# SCH_Remote_Recovery_Switch_Mini_v1_2025-.net
KiCad netlist of a schematic drawn in EasyEDA
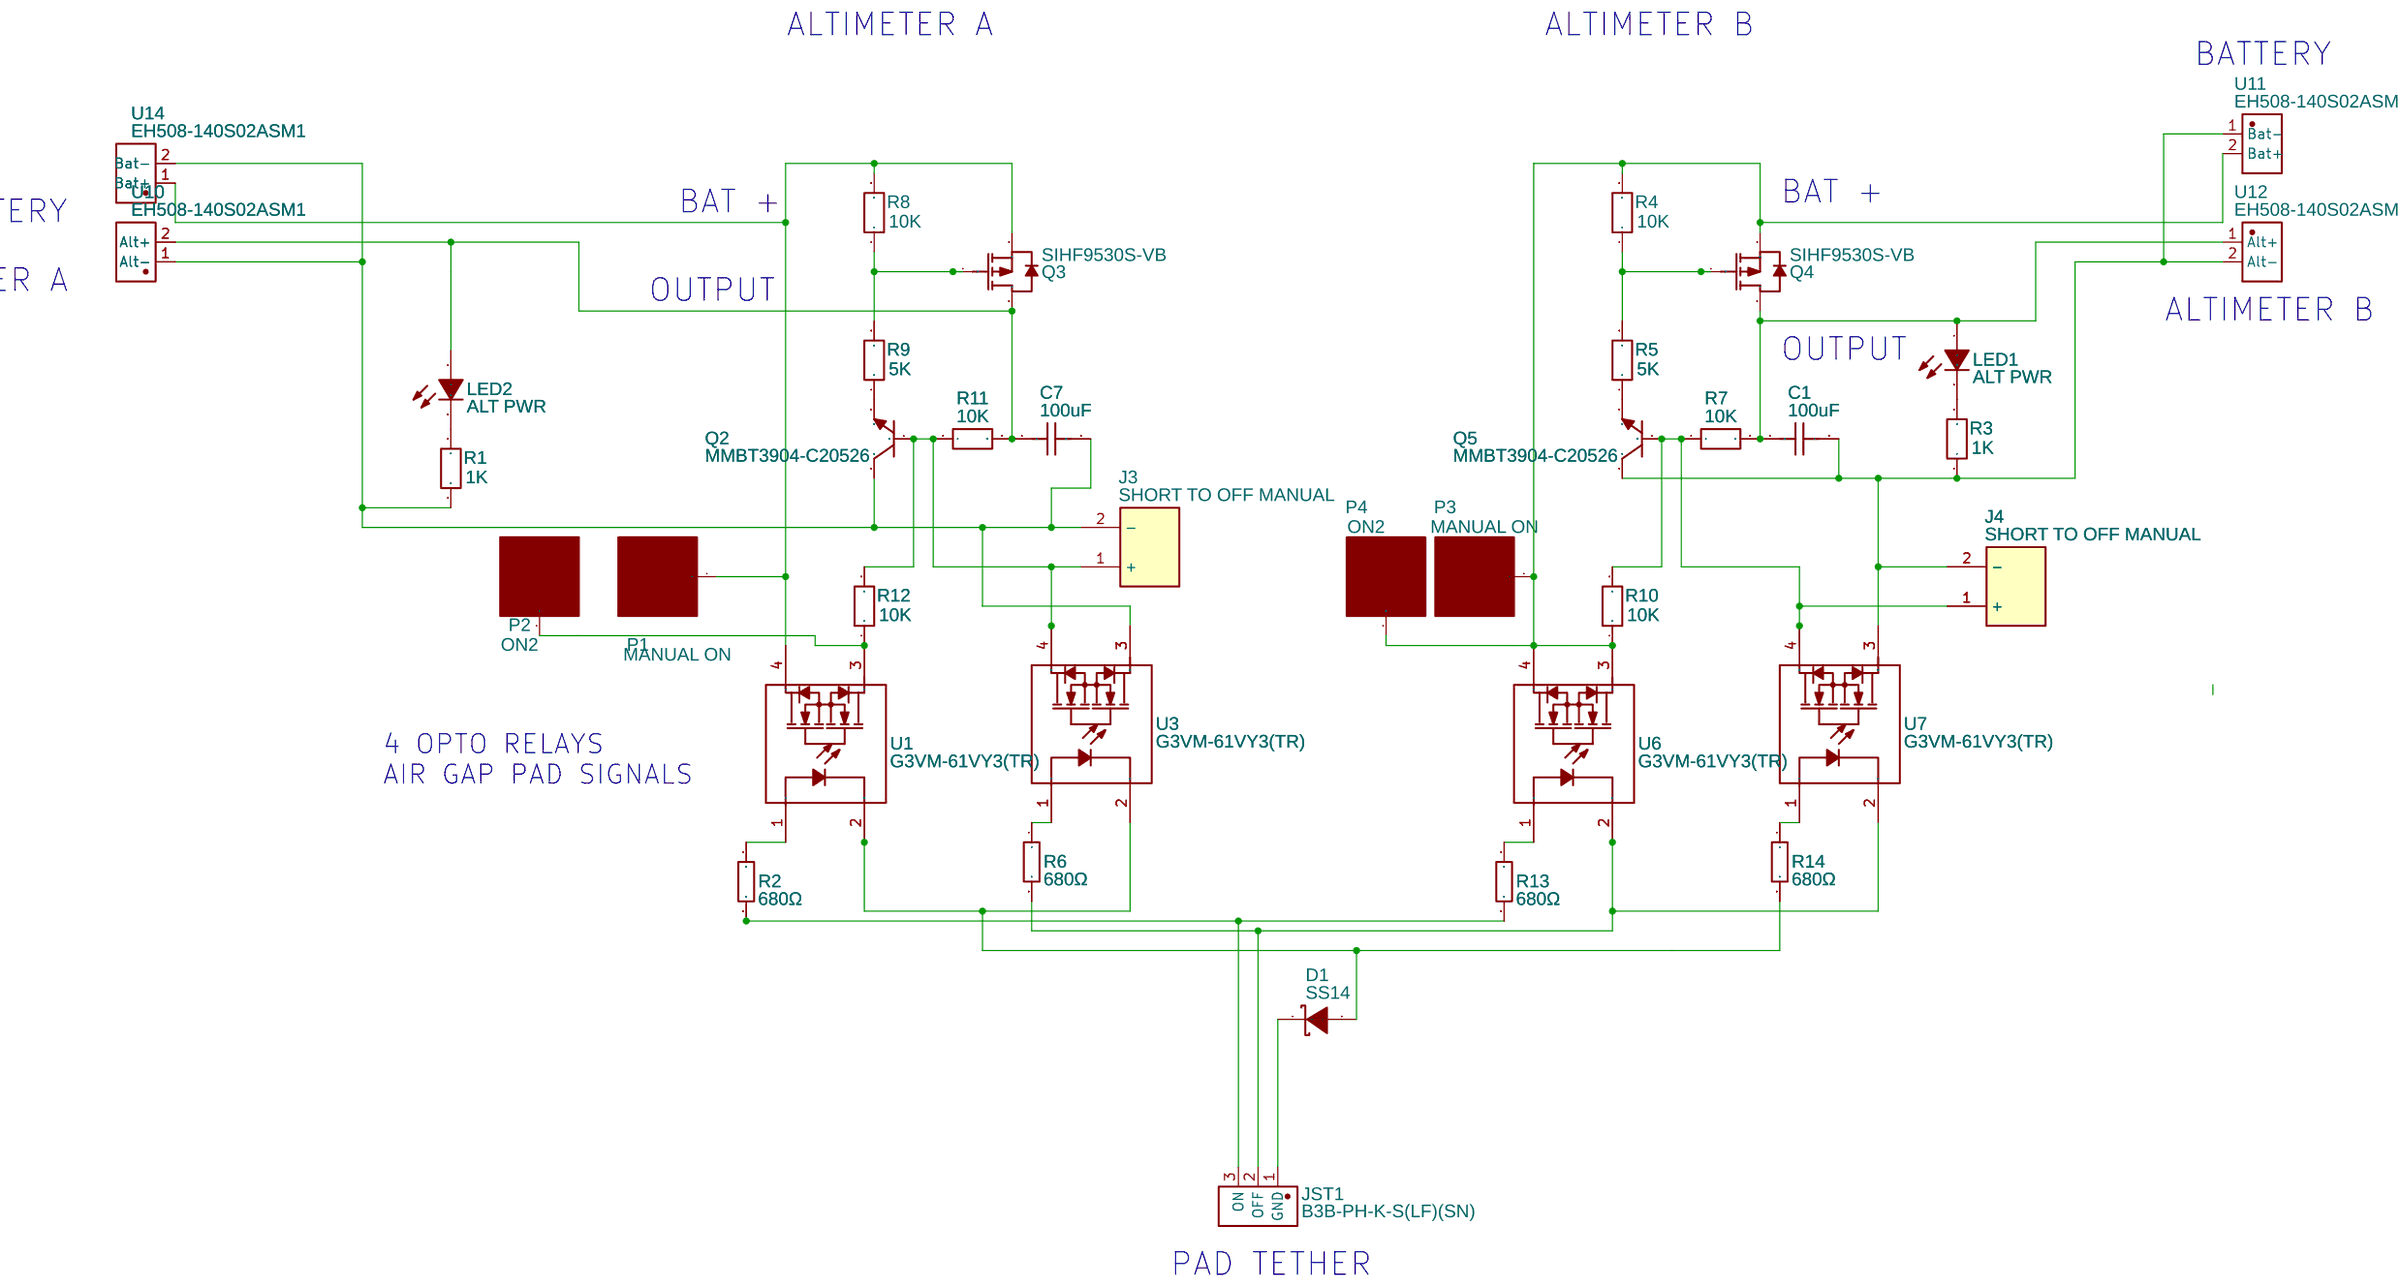
[diagram p0: schematic sheet]

(export (version "E")
  (design (tool "Eeschema 10.0.6"))
  (components
    (comp (ref "C1")
      (value "100uF")
      (fields
        (field (name "Manufacturer Part") "GRM31CR61A107MEA8L")
        (field (name "Manufacturer") "muRata(村田)")
      )
      (libsource (lib "") (part "GRM31CR61A107MEA8L"))
    )
    (comp (ref "C7")
      (value "100uF")
      (fields
        (field (name "Manufacturer Part") "GRM31CR61A107MEA8L")
        (field (name "Manufacturer") "muRata(村田)")
      )
      (libsource (lib "") (part "GRM31CR61A107MEA8L"))
    )
    (comp (ref "D1")
      (value "SS14")
      (fields (field (name "Manufacturer") "MDD(辰达半导体)"))
      (libsource (lib "") (part "SS14"))
    )
    (comp (ref "J3")
      (value "SHORT TO OFF MANUAL")
      (fields (field (name "Manufacturer Part") "B2B-PH-K-S(LF)(SN)") (field (name "Manufacturer") "JST"))
      (libsource (lib "") (part "B2B-PH-K-S(LF)(SN)"))
    )
    (comp (ref "J4")
      (value "SHORT TO OFF MANUAL")
      (fields (field (name "Manufacturer Part") "B2B-PH-K-S(LF)(SN)") (field (name "Manufacturer") "JST"))
      (libsource (lib "") (part "B2B-PH-K-S(LF)(SN)"))
    )
    (comp (ref "JST1")
      (value "B3B-PH-K-S(LF)(SN)")
      (fields (field (name "Manufacturer") "JST"))
      (libsource (lib "") (part "B3B-PH-K-S(LF)(SN)"))
    )
    (comp (ref "LED1")
      (value "ALT PWR")
      (fields
        (field (name "Manufacturer Part") "67-21/R6C-FN2Q1BZ/2T")
        (field (name "Manufacturer") "EVERLIGHT")
      )
      (libsource (lib "") (part "67-21/R6C-FN2Q1BZ/2T"))
    )
    (comp (ref "LED2")
      (value "ALT PWR")
      (fields
        (field (name "Manufacturer Part") "67-21/R6C-FN2Q1BZ/2T")
        (field (name "Manufacturer") "EVERLIGHT")
      )
      (libsource (lib "") (part "67-21/R6C-FN2Q1BZ/2T"))
    )
    (comp (ref "P1")
      (value "MANUAL ON")
      (fields (field (name "Manufacturer Part") "Soldering pad"))
      (libsource (lib "") (part "Solder Pad"))
    )
    (comp (ref "P2")
      (value "ON2")
      (fields (field (name "Manufacturer Part") "Soldering pad"))
      (libsource (lib "") (part "Solder Pad_1"))
    )
    (comp (ref "P3")
      (value "MANUAL ON")
      (fields (field (name "Manufacturer Part") "Soldering pad"))
      (libsource (lib "") (part "Solder Pad"))
    )
    (comp (ref "P4")
      (value "ON2")
      (fields (field (name "Manufacturer Part") "Soldering pad"))
      (libsource (lib "") (part "Solder Pad_1"))
    )
    (comp (ref "Q2")
      (value "MMBT3904-C20526")
      (fields
        (field (name "Manufacturer Part") "MMBT3904(RANGE:100-300)")
        (field (name "Manufacturer") "CJ(江苏长电/长晶)")
      )
      (libsource (lib "") (part "MMBT3904-C20526"))
    )
    (comp (ref "Q3")
      (value "SIHF9530S-VB")
      (fields (field (name "Manufacturer Part") "SiHF9530S-VB") (field (name "Manufacturer") "VBsemi(微碧半导体)"))
      (libsource (lib "") (part "SIHF9530S-VB"))
    )
    (comp (ref "Q4")
      (value "SIHF9530S-VB")
      (fields (field (name "Manufacturer Part") "SiHF9530S-VB") (field (name "Manufacturer") "VBsemi(微碧半导体)"))
      (libsource (lib "") (part "SIHF9530S-VB"))
    )
    (comp (ref "Q5")
      (value "MMBT3904-C20526")
      (fields
        (field (name "Manufacturer Part") "MMBT3904(RANGE:100-300)")
        (field (name "Manufacturer") "CJ(江苏长电/长晶)")
      )
      (libsource (lib "") (part "MMBT3904-C20526"))
    )
    (comp (ref "R1")
      (value "1K")
      (fields (field (name "Manufacturer Part") "SFR03EZPF1001") (field (name "Manufacturer") "ROHM(罗姆)"))
      (libsource (lib "") (part "SFR03EZPF1001"))
    )
    (comp (ref "R2")
      (value "680Ω")
      (fields
        (field (name "Manufacturer Part") "0603WAF6800T5E")
        (field (name "Manufacturer") "UNI-ROYAL(厚声)")
      )
      (libsource (lib "") (part "0603WAF6800T5E"))
    )
    (comp (ref "R3")
      (value "1K")
      (fields (field (name "Manufacturer Part") "SFR03EZPF1001") (field (name "Manufacturer") "ROHM(罗姆)"))
      (libsource (lib "") (part "SFR03EZPF1001"))
    )
    (comp (ref "R4")
      (value "10K")
      (fields (field (name "Manufacturer Part") "SFR03EZPF1001") (field (name "Manufacturer") "ROHM(罗姆)"))
      (libsource (lib "") (part "SFR03EZPF1001"))
    )
    (comp (ref "R5")
      (value "5K")
      (fields (field (name "Manufacturer Part") "SFR03EZPF1001") (field (name "Manufacturer") "ROHM(罗姆)"))
      (libsource (lib "") (part "SFR03EZPF1001"))
    )
    (comp (ref "R6")
      (value "680Ω")
      (fields
        (field (name "Manufacturer Part") "0603WAF6800T5E")
        (field (name "Manufacturer") "UNI-ROYAL(厚声)")
      )
      (libsource (lib "") (part "0603WAF6800T5E"))
    )
    (comp (ref "R7")
      (value "10K")
      (fields (field (name "Manufacturer Part") "SFR03EZPF1001") (field (name "Manufacturer") "ROHM(罗姆)"))
      (libsource (lib "") (part "SFR03EZPF1001_1"))
    )
    (comp (ref "R8")
      (value "10K")
      (fields (field (name "Manufacturer Part") "SFR03EZPF1001") (field (name "Manufacturer") "ROHM(罗姆)"))
      (libsource (lib "") (part "SFR03EZPF1001"))
    )
    (comp (ref "R9")
      (value "5K")
      (fields (field (name "Manufacturer Part") "SFR03EZPF1001") (field (name "Manufacturer") "ROHM(罗姆)"))
      (libsource (lib "") (part "SFR03EZPF1001"))
    )
    (comp (ref "R10")
      (value "10K")
      (fields (field (name "Manufacturer Part") "SFR03EZPF1001") (field (name "Manufacturer") "ROHM(罗姆)"))
      (libsource (lib "") (part "SFR03EZPF1001"))
    )
    (comp (ref "R11")
      (value "10K")
      (fields (field (name "Manufacturer Part") "SFR03EZPF1001") (field (name "Manufacturer") "ROHM(罗姆)"))
      (libsource (lib "") (part "SFR03EZPF1001_1"))
    )
    (comp (ref "R12")
      (value "10K")
      (fields (field (name "Manufacturer Part") "SFR03EZPF1001") (field (name "Manufacturer") "ROHM(罗姆)"))
      (libsource (lib "") (part "SFR03EZPF1001"))
    )
    (comp (ref "R13")
      (value "680Ω")
      (fields
        (field (name "Manufacturer Part") "0603WAF6800T5E")
        (field (name "Manufacturer") "UNI-ROYAL(厚声)")
      )
      (libsource (lib "") (part "0603WAF6800T5E"))
    )
    (comp (ref "R14")
      (value "680Ω")
      (fields
        (field (name "Manufacturer Part") "0603WAF6800T5E")
        (field (name "Manufacturer") "UNI-ROYAL(厚声)")
      )
      (libsource (lib "") (part "0603WAF6800T5E"))
    )
    (comp (ref "U1")
      (value "G3VM-61VY3(TR)")
      (fields (field (name "Manufacturer") "OMRON(欧姆龙)"))
      (libsource (lib "") (part "G3VM-61VY3(TR)"))
    )
    (comp (ref "U3")
      (value "G3VM-61VY3(TR)")
      (fields (field (name "Manufacturer") "OMRON(欧姆龙)"))
      (libsource (lib "") (part "G3VM-61VY3(TR)"))
    )
    (comp (ref "U6")
      (value "G3VM-61VY3(TR)")
      (fields (field (name "Manufacturer") "OMRON(欧姆龙)"))
      (libsource (lib "") (part "G3VM-61VY3(TR)"))
    )
    (comp (ref "U7")
      (value "G3VM-61VY3(TR)")
      (fields (field (name "Manufacturer") "OMRON(欧姆龙)"))
      (libsource (lib "") (part "G3VM-61VY3(TR)"))
    )
    (comp (ref "U10")
      (value "EH508-140S02ASM1")
      (fields (field (name "Manufacturer") "Wcon(维峰电子)"))
      (libsource (lib "") (part "EH508-140S02ASM1_1"))
    )
    (comp (ref "U11")
      (value "EH508-140S02ASM1")
      (fields (field (name "Manufacturer") "Wcon(维峰电子)"))
      (libsource (lib "") (part "EH508-140S02ASM1"))
    )
    (comp (ref "U12")
      (value "EH508-140S02ASM1")
      (fields (field (name "Manufacturer") "Wcon(维峰电子)"))
      (libsource (lib "") (part "EH508-140S02ASM1_3"))
    )
    (comp (ref "U14")
      (value "EH508-140S02ASM1")
      (fields (field (name "Manufacturer") "Wcon(维峰电子)"))
      (libsource (lib "") (part "EH508-140S02ASM1_2"))
    )
  )
  (nets
    (net (code "1") (name "Net-(D1-A)") (class "Default")
      (node (ref "D1") (pin "2") (pinfunction "A_2") (pintype "unspecified"))
      (node (ref "R14") (pin "2") (pinfunction "2_2") (pintype "input"))
      (node (ref "U1") (pin "2") (pinfunction "2_2") (pintype "unspecified"))
      (node (ref "U3") (pin "2") (pinfunction "2_2") (pintype "unspecified"))
    )
    (net (code "2") (name "Net-(D1-K)") (class "Default")
      (node (ref "D1") (pin "1") (pinfunction "K_1") (pintype "unspecified"))
      (node (ref "JST1") (pin "1") (pinfunction "GND_1") (pintype "unspecified"))
    )
    (net (code "3") (name "Net-(J3-+)") (class "Default")
      (node (ref "J3") (pin "1") (pinfunction "+_1") (pintype "input"))
      (node (ref "Q2") (pin "1") (pinfunction "B_1") (pintype "unspecified"))
      (node (ref "R11") (pin "1") (pinfunction "1_1") (pintype "unspecified"))
      (node (ref "R12") (pin "2") (pinfunction "2_2") (pintype "unspecified"))
      (node (ref "U3") (pin "4") (pinfunction "4_4") (pintype "unspecified"))
    )
    (net (code "4") (name "Net-(J3--)") (class "Default")
      (node (ref "C7") (pin "2") (pinfunction "2_2") (pintype "unspecified"))
      (node (ref "J3") (pin "2") (pinfunction "-_2") (pintype "input"))
      (node (ref "Q2") (pin "3") (pinfunction "C_3") (pintype "unspecified"))
      (node (ref "R1") (pin "1") (pinfunction "1_1") (pintype "unspecified"))
      (node (ref "U10") (pin "1") (pinfunction "Alt-_1") (pintype "unspecified"))
      (node (ref "U14") (pin "2") (pinfunction "Bat-_2") (pintype "unspecified"))
      (node (ref "U3") (pin "3") (pinfunction "3_3") (pintype "unspecified"))
    )
    (net (code "5") (name "Net-(J4-+)") (class "Default")
      (node (ref "J4") (pin "1") (pinfunction "+_1") (pintype "input"))
      (node (ref "Q5") (pin "1") (pinfunction "B_1") (pintype "unspecified"))
      (node (ref "R10") (pin "2") (pinfunction "2_2") (pintype "unspecified"))
      (node (ref "R7") (pin "1") (pinfunction "1_1") (pintype "unspecified"))
      (node (ref "U7") (pin "4") (pinfunction "4_4") (pintype "unspecified"))
    )
    (net (code "6") (name "Net-(J4--)") (class "Default")
      (node (ref "C1") (pin "2") (pinfunction "2_2") (pintype "unspecified"))
      (node (ref "J4") (pin "2") (pinfunction "-_2") (pintype "input"))
      (node (ref "Q5") (pin "3") (pinfunction "C_3") (pintype "unspecified"))
      (node (ref "R3") (pin "1") (pinfunction "1_1") (pintype "unspecified"))
      (node (ref "U11") (pin "1") (pinfunction "Bat-_1") (pintype "unspecified"))
      (node (ref "U12") (pin "2") (pinfunction "Alt-_2") (pintype "unspecified"))
      (node (ref "U7") (pin "3") (pinfunction "3_3") (pintype "unspecified"))
    )
    (net (code "7") (name "Net-(JST1-OFF)") (class "Default")
      (node (ref "JST1") (pin "2") (pinfunction "OFF_2") (pintype "unspecified"))
      (node (ref "R6") (pin "2") (pinfunction "2_2") (pintype "input"))
      (node (ref "U6") (pin "2") (pinfunction "2_2") (pintype "unspecified"))
      (node (ref "U7") (pin "2") (pinfunction "2_2") (pintype "unspecified"))
    )
    (net (code "8") (name "Net-(JST1-ON)") (class "Default")
      (node (ref "JST1") (pin "3") (pinfunction "ON_3") (pintype "unspecified"))
      (node (ref "R13") (pin "2") (pinfunction "2_2") (pintype "input"))
      (node (ref "R2") (pin "2") (pinfunction "2_2") (pintype "input"))
    )
    (net (code "9") (name "Net-(LED1-A)") (class "Default")
      (node (ref "C1") (pin "1") (pinfunction "1_1") (pintype "unspecified"))
      (node (ref "LED1") (pin "1") (pinfunction "A_1") (pintype "input"))
      (node (ref "Q4") (pin "2") (pinfunction "D_2") (pintype "unspecified"))
      (node (ref "R7") (pin "2") (pinfunction "2_2") (pintype "unspecified"))
      (node (ref "U12") (pin "1") (pinfunction "Alt+_1") (pintype "unspecified"))
    )
    (net (code "10") (name "Net-(LED1-C)") (class "Default")
      (node (ref "LED1") (pin "2") (pinfunction "C_2") (pintype "input"))
      (node (ref "R3") (pin "2") (pinfunction "2_2") (pintype "unspecified"))
    )
    (net (code "11") (name "Net-(LED2-A)") (class "Default")
      (node (ref "C7") (pin "1") (pinfunction "1_1") (pintype "unspecified"))
      (node (ref "LED2") (pin "1") (pinfunction "A_1") (pintype "input"))
      (node (ref "Q3") (pin "2") (pinfunction "D_2") (pintype "unspecified"))
      (node (ref "R11") (pin "2") (pinfunction "2_2") (pintype "unspecified"))
      (node (ref "U10") (pin "2") (pinfunction "Alt+_2") (pintype "unspecified"))
    )
    (net (code "12") (name "Net-(LED2-C)") (class "Default")
      (node (ref "LED2") (pin "2") (pinfunction "C_2") (pintype "input"))
      (node (ref "R1") (pin "2") (pinfunction "2_2") (pintype "unspecified"))
    )
    (net (code "13") (name "Net-(P2-Pad1)") (class "Default")
      (node (ref "P2") (pin "1") (pinfunction "1_1") (pintype "unspecified"))
      (node (ref "R12") (pin "1") (pinfunction "1_1") (pintype "unspecified"))
      (node (ref "U1") (pin "3") (pinfunction "3_3") (pintype "unspecified"))
    )
    (net (code "14") (name "Net-(Q2-E)") (class "Default")
      (node (ref "Q2") (pin "2") (pinfunction "E_2") (pintype "unspecified"))
      (node (ref "R9") (pin "1") (pinfunction "1_1") (pintype "unspecified"))
    )
    (net (code "15") (name "Net-(Q3-G)") (class "Default")
      (node (ref "Q3") (pin "1") (pinfunction "G_1") (pintype "unspecified"))
      (node (ref "R8") (pin "1") (pinfunction "1_1") (pintype "unspecified"))
      (node (ref "R9") (pin "2") (pinfunction "2_2") (pintype "unspecified"))
    )
    (net (code "16") (name "Net-(Q3-S)") (class "Default")
      (node (ref "P1") (pin "1") (pinfunction "1_1") (pintype "unspecified"))
      (node (ref "Q3") (pin "3") (pinfunction "S_3") (pintype "unspecified"))
      (node (ref "R8") (pin "2") (pinfunction "2_2") (pintype "unspecified"))
      (node (ref "U1") (pin "4") (pinfunction "4_4") (pintype "unspecified"))
      (node (ref "U14") (pin "1") (pinfunction "Bat+_1") (pintype "unspecified"))
    )
    (net (code "17") (name "Net-(Q4-G)") (class "Default")
      (node (ref "Q4") (pin "1") (pinfunction "G_1") (pintype "unspecified"))
      (node (ref "R4") (pin "1") (pinfunction "1_1") (pintype "unspecified"))
      (node (ref "R5") (pin "2") (pinfunction "2_2") (pintype "unspecified"))
    )
    (net (code "18") (name "Net-(Q4-S)") (class "Default")
      (node (ref "P3") (pin "1") (pinfunction "1_1") (pintype "unspecified"))
      (node (ref "P4") (pin "1") (pinfunction "1_1") (pintype "unspecified"))
      (node (ref "Q4") (pin "3") (pinfunction "S_3") (pintype "unspecified"))
      (node (ref "R10") (pin "1") (pinfunction "1_1") (pintype "unspecified"))
      (node (ref "R4") (pin "2") (pinfunction "2_2") (pintype "unspecified"))
      (node (ref "U11") (pin "2") (pinfunction "Bat+_2") (pintype "unspecified"))
      (node (ref "U6") (pin "3") (pinfunction "3_3") (pintype "unspecified"))
      (node (ref "U6") (pin "4") (pinfunction "4_4") (pintype "unspecified"))
    )
    (net (code "19") (name "Net-(Q5-E)") (class "Default")
      (node (ref "Q5") (pin "2") (pinfunction "E_2") (pintype "unspecified"))
      (node (ref "R5") (pin "1") (pinfunction "1_1") (pintype "unspecified"))
    )
    (net (code "20") (name "Net-(R2-Pad1)") (class "Default")
      (node (ref "R2") (pin "1") (pinfunction "1_1") (pintype "input"))
      (node (ref "U1") (pin "1") (pinfunction "1_1") (pintype "unspecified"))
    )
    (net (code "21") (name "Net-(R6-Pad1)") (class "Default")
      (node (ref "R6") (pin "1") (pinfunction "1_1") (pintype "input"))
      (node (ref "U3") (pin "1") (pinfunction "1_1") (pintype "unspecified"))
    )
    (net (code "22") (name "Net-(R13-Pad1)") (class "Default")
      (node (ref "R13") (pin "1") (pinfunction "1_1") (pintype "input"))
      (node (ref "U6") (pin "1") (pinfunction "1_1") (pintype "unspecified"))
    )
    (net (code "23") (name "Net-(R14-Pad1)") (class "Default")
      (node (ref "R14") (pin "1") (pinfunction "1_1") (pintype "input"))
      (node (ref "U7") (pin "1") (pinfunction "1_1") (pintype "unspecified"))
    )
  )
)
